# Stepper_control.net
KiCad netlist of a schematic drawn in Altium Designer
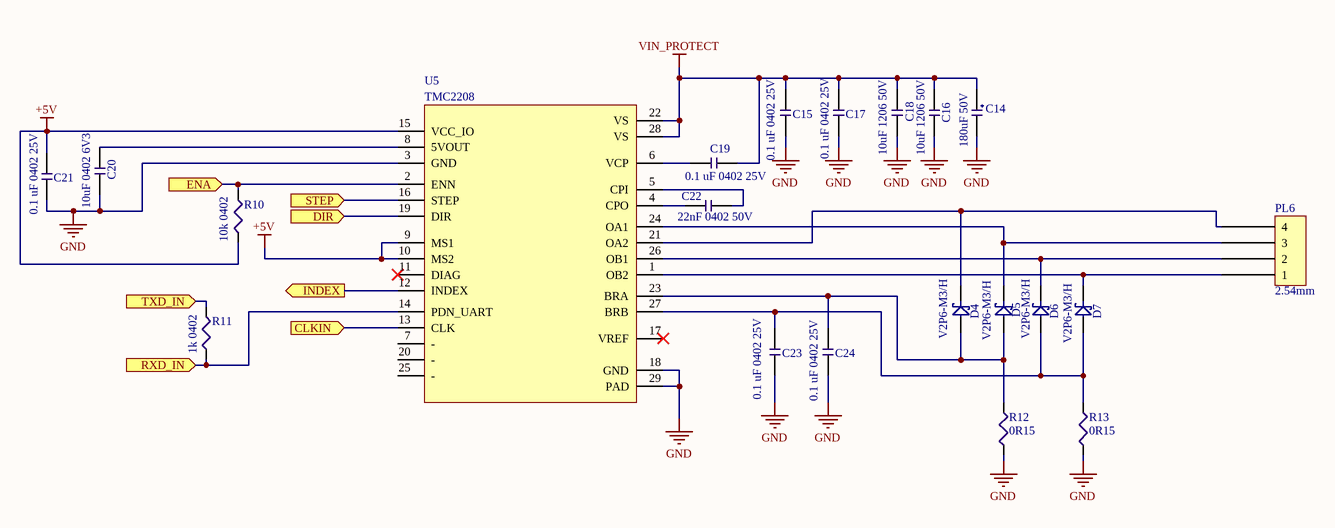
[diagram p0: Stepper_control.SchDoc]

(export (version "E")
  (design (tool "Eeschema 10.0.6"))
  (components
    (comp (ref "C14")
      (value "180uF 50V")
      (footprint "Capacitor 8x22")
      (description "180UF 20% 50V 105DEG RADIAL")
      (fields (field (name "TOLERANCE") "20%"))
      (libsource (lib "ON Development Vault") (part "Polar capacitor"))
    )
    (comp (ref "C15")
      (value "0.1 uF 0402 25V")
      (footprint "CAP_0402")
      (description "0.1UF 25V 10% X5R 0402")
      (fields (field (name "TOLERANCE") "10%") (field (name "VOLTAGE") "25V"))
      (libsource (lib "ON Development Vault") (part "Capacitor"))
    )
    (comp (ref "C16")
      (value "10uF 1206 50V")
      (footprint "CAP_1206")
      (description "10uF 1206 50V X5R 20%")
      (fields (field (name "TOLERANCE") "+/- 20%") (field (name "VOLTAGE") "50 V"))
      (libsource (lib "ON Development Vault") (part "Capacitor"))
    )
    (comp (ref "C17")
      (value "0.1 uF 0402 25V")
      (footprint "CAP_0402")
      (description "0.1UF 25V 10% X5R 0402")
      (fields (field (name "TOLERANCE") "10%") (field (name "VOLTAGE") "25V"))
      (libsource (lib "ON Development Vault") (part "Capacitor"))
    )
    (comp (ref "C18")
      (value "10uF 1206 50V")
      (footprint "CAP_1206")
      (description "10uF 1206 50V X5R 20%")
      (fields (field (name "TOLERANCE") "+/- 20%") (field (name "VOLTAGE") "50 V"))
      (libsource (lib "ON Development Vault") (part "Capacitor"))
    )
    (comp (ref "C19")
      (value "0.1 uF 0402 25V")
      (footprint "CAP_0402")
      (description "0.1UF 25V 10% X5R 0402")
      (fields (field (name "TOLERANCE") "10%") (field (name "VOLTAGE") "25V"))
      (libsource (lib "ON Development Vault") (part "Capacitor"))
    )
    (comp (ref "C20")
      (value "10uF 0402 6V3")
      (footprint "CAP_0402")
      (description "10uF 20% 0402 6V3 X6S")
      (fields (field (name "TOLERANCE") "20%") (field (name "VOLTAGE") "6V3"))
      (libsource (lib "ON Development Vault") (part "Capacitor"))
    )
    (comp (ref "C21")
      (value "0.1 uF 0402 25V")
      (footprint "CAP_0402")
      (description "0.1UF 25V 10% X5R 0402")
      (fields (field (name "TOLERANCE") "10%") (field (name "VOLTAGE") "25V"))
      (libsource (lib "ON Development Vault") (part "Capacitor"))
    )
    (comp (ref "C22")
      (value "22nF 0402 50V")
      (footprint "CAP_0402")
      (description "22nF 0402 50V X7R 10%")
      (fields (field (name "TOLERANCE") "10%") (field (name "VOLTAGE") "50V"))
      (libsource (lib "ON Development Vault") (part "Capacitor"))
    )
    (comp (ref "C23")
      (value "0.1 uF 0402 25V")
      (footprint "CAP_0402")
      (description "0.1UF 25V 10% X5R 0402")
      (fields (field (name "TOLERANCE") "10%") (field (name "VOLTAGE") "25V"))
      (libsource (lib "ON Development Vault") (part "Capacitor"))
    )
    (comp (ref "C24")
      (value "0.1 uF 0402 25V")
      (footprint "CAP_0402")
      (description "0.1UF 25V 10% X5R 0402")
      (fields (field (name "TOLERANCE") "10%") (field (name "VOLTAGE") "25V"))
      (libsource (lib "ON Development Vault") (part "Capacitor"))
    )
    (comp (ref "D4")
      (value "V2P6-M3/H")
      (footprint "MicroSMP")
      (description "DIODE SCHOTTKY 60V 2A MICROSMP")
      (libsource (lib "ON Development Vault") (part "Schottky"))
    )
    (comp (ref "D5")
      (value "V2P6-M3/H")
      (footprint "MicroSMP")
      (description "DIODE SCHOTTKY 60V 2A MICROSMP")
      (libsource (lib "ON Development Vault") (part "Schottky"))
    )
    (comp (ref "D6")
      (value "V2P6-M3/H")
      (footprint "MicroSMP")
      (description "DIODE SCHOTTKY 60V 2A MICROSMP")
      (libsource (lib "ON Development Vault") (part "Schottky"))
    )
    (comp (ref "D7")
      (value "V2P6-M3/H")
      (footprint "MicroSMP")
      (description "DIODE SCHOTTKY 60V 2A MICROSMP")
      (libsource (lib "ON Development Vault") (part "Schottky"))
    )
    (comp (ref "PL6")
      (value "2.54mm")
      (footprint "4-pin 2.54mm header")
      (description "Pin header 4-pin 2.54mm male")
      (fields (field (name "MFG. PART NUMBER") "DS1021-1*4SF1-1"))
      (libsource (lib "ON Development Vault") (part "4-pin header"))
    )
    (comp (ref "R10")
      (value "10k 0402")
      (footprint "RES_0402")
      (description "RES SMD 10K OHM 1% 1/16W 0402")
      (fields (field (name "POWER") "1/16 W") (field (name "TOLERANCE") "1 %"))
      (libsource (lib "ON Development Vault") (part "Resistor"))
    )
    (comp (ref "R11")
      (value "1k 0402")
      (footprint "RES_0402")
      (description "RES SMD 1K OHM 1% 1/16W 0402")
      (fields (field (name "POWER") "1/16W") (field (name "TOLERANCE") "1%"))
      (libsource (lib "ON Development Vault") (part "Resistor"))
    )
    (comp (ref "R12")
      (value "0R15")
      (footprint "RES_1206")
      (description "RES 0.15 OHM 1% 1/2W 1206")
      (fields (field (name "TOLERANCE") "1%") (field (name "POWER") "0.5W"))
      (libsource (lib "ON Development Vault") (part "Resistor"))
    )
    (comp (ref "R13")
      (value "0R15")
      (footprint "RES_1206")
      (description "RES 0.15 OHM 1% 1/2W 1206")
      (fields (field (name "TOLERANCE") "1%") (field (name "POWER") "0.5W"))
      (libsource (lib "ON Development Vault") (part "Resistor"))
    )
    (comp (ref "U5")
      (value "TMC2208")
      (footprint "QFN50P500X500X90_HS-29N")
      (description "IC STEPPER MOTOR DRIVER 28QFN")
      (fields (field (name "MFG. PART NUMBER") "TMC2208-LA-T"))
      (libsource (lib "ON Development Vault") (part "TMC2208"))
    )
  )
  (nets
    (net (code "1") (name "+5V") (class "Default")
      (node (ref "C21") (pin "2") (pinfunction "2_2") (pintype "passive"))
      (node (ref "R10") (pin "2") (pinfunction "2_2") (pintype "passive"))
      (node (ref "U5") (pin "10") (pinfunction "MS2_10") (pintype "passive"))
      (node (ref "U5") (pin "15") (pinfunction "VCC_IO_15") (pintype "passive"))
      (node (ref "U5") (pin "9") (pinfunction "MS1_9") (pintype "passive"))
    )
    (net (code "2") (name "/CLKIN") (class "Default")
      (node (ref "U5") (pin "13") (pinfunction "CLK_13") (pintype "passive"))
    )
    (net (code "3") (name "/DIR") (class "Default")
      (node (ref "U5") (pin "19") (pinfunction "DIR_19") (pintype "passive"))
    )
    (net (code "4") (name "/ENA") (class "Default")
      (node (ref "R10") (pin "1") (pinfunction "1_1") (pintype "passive"))
      (node (ref "U5") (pin "2") (pinfunction "ENN_2") (pintype "passive"))
    )
    (net (code "5") (name "/INDEX") (class "Default")
      (node (ref "U5") (pin "12") (pinfunction "INDEX_12") (pintype "passive"))
    )
    (net (code "6") (name "/RXD_IN") (class "Default")
      (node (ref "R11") (pin "1") (pinfunction "1_1") (pintype "passive"))
      (node (ref "U5") (pin "14") (pinfunction "PDN_UART_14") (pintype "passive"))
    )
    (net (code "7") (name "/STEP") (class "Default")
      (node (ref "U5") (pin "16") (pinfunction "STEP_16") (pintype "passive"))
    )
    (net (code "8") (name "/TXD_IN") (class "Default")
      (node (ref "R11") (pin "2") (pinfunction "2_2") (pintype "passive"))
    )
    (net (code "9") (name "GND") (class "Default")
      (node (ref "C14") (pin "2") (pinfunction "2_2") (pintype "passive"))
      (node (ref "C15") (pin "1") (pinfunction "1_1") (pintype "passive"))
      (node (ref "C16") (pin "2") (pinfunction "2_2") (pintype "passive"))
      (node (ref "C17") (pin "1") (pinfunction "1_1") (pintype "passive"))
      (node (ref "C18") (pin "2") (pinfunction "2_2") (pintype "passive"))
      (node (ref "C20") (pin "1") (pinfunction "1_1") (pintype "passive"))
      (node (ref "C21") (pin "1") (pinfunction "1_1") (pintype "passive"))
      (node (ref "C23") (pin "1") (pinfunction "1_1") (pintype "passive"))
      (node (ref "C24") (pin "1") (pinfunction "1_1") (pintype "passive"))
      (node (ref "R12") (pin "1") (pinfunction "1_1") (pintype "passive"))
      (node (ref "R13") (pin "1") (pinfunction "1_1") (pintype "passive"))
      (node (ref "U5") (pin "18") (pinfunction "GND_18") (pintype "passive"))
      (node (ref "U5") (pin "29") (pinfunction "PAD_29") (pintype "passive"))
      (node (ref "U5") (pin "3") (pinfunction "GND_3") (pintype "passive"))
    )
    (net (code "10") (name "Net-(U5-5VOUT)") (class "Default")
      (node (ref "C20") (pin "2") (pinfunction "2_2") (pintype "passive"))
      (node (ref "U5") (pin "8") (pinfunction "5VOUT_8") (pintype "passive"))
    )
    (net (code "11") (name "Net-(U5-BRA)") (class "Default")
      (node (ref "C24") (pin "2") (pinfunction "2_2") (pintype "passive"))
      (node (ref "D4") (pin "1") (pinfunction "1_1") (pintype "passive"))
      (node (ref "D5") (pin "1") (pinfunction "1_1") (pintype "passive"))
      (node (ref "R12") (pin "2") (pinfunction "2_2") (pintype "passive"))
      (node (ref "U5") (pin "23") (pinfunction "BRA_23") (pintype "passive"))
    )
    (net (code "12") (name "Net-(U5-BRB)") (class "Default")
      (node (ref "C23") (pin "2") (pinfunction "2_2") (pintype "passive"))
      (node (ref "D6") (pin "1") (pinfunction "1_1") (pintype "passive"))
      (node (ref "D7") (pin "1") (pinfunction "1_1") (pintype "passive"))
      (node (ref "R13") (pin "2") (pinfunction "2_2") (pintype "passive"))
      (node (ref "U5") (pin "27") (pinfunction "BRB_27") (pintype "passive"))
    )
    (net (code "13") (name "Net-(U5-CPI)") (class "Default")
      (node (ref "C22") (pin "2") (pinfunction "2_2") (pintype "passive"))
      (node (ref "U5") (pin "5") (pinfunction "CPI_5") (pintype "passive"))
    )
    (net (code "14") (name "Net-(U5-CPO)") (class "Default")
      (node (ref "C22") (pin "1") (pinfunction "1_1") (pintype "passive"))
      (node (ref "U5") (pin "4") (pinfunction "CPO_4") (pintype "passive"))
    )
    (net (code "15") (name "Net-(U5-OA1)") (class "Default")
      (node (ref "D5") (pin "2") (pinfunction "2_2") (pintype "passive"))
      (node (ref "PL6") (pin "3") (pinfunction "3_3") (pintype "passive"))
      (node (ref "U5") (pin "24") (pinfunction "OA1_24") (pintype "passive"))
    )
    (net (code "16") (name "Net-(U5-OA2)") (class "Default")
      (node (ref "D4") (pin "2") (pinfunction "2_2") (pintype "passive"))
      (node (ref "PL6") (pin "4") (pinfunction "4_4") (pintype "passive"))
      (node (ref "U5") (pin "21") (pinfunction "OA2_21") (pintype "passive"))
    )
    (net (code "17") (name "Net-(U5-OB1)") (class "Default")
      (node (ref "D6") (pin "2") (pinfunction "2_2") (pintype "passive"))
      (node (ref "PL6") (pin "2") (pinfunction "2_2") (pintype "passive"))
      (node (ref "U5") (pin "26") (pinfunction "OB1_26") (pintype "passive"))
    )
    (net (code "18") (name "Net-(U5-OB2)") (class "Default")
      (node (ref "D7") (pin "2") (pinfunction "2_2") (pintype "passive"))
      (node (ref "PL6") (pin "1") (pinfunction "1_1") (pintype "passive"))
      (node (ref "U5") (pin "1") (pinfunction "OB2_1") (pintype "passive"))
    )
    (net (code "19") (name "Net-(U5-VCP)") (class "Default")
      (node (ref "C19") (pin "2") (pinfunction "2_2") (pintype "passive"))
      (node (ref "U5") (pin "6") (pinfunction "VCP_6") (pintype "passive"))
    )
    (net (code "20") (name "VIN_PROTECT") (class "Default")
      (node (ref "C14") (pin "1") (pinfunction "1_1") (pintype "passive"))
      (node (ref "C15") (pin "2") (pinfunction "2_2") (pintype "passive"))
      (node (ref "C16") (pin "1") (pinfunction "1_1") (pintype "passive"))
      (node (ref "C17") (pin "2") (pinfunction "2_2") (pintype "passive"))
      (node (ref "C18") (pin "1") (pinfunction "1_1") (pintype "passive"))
      (node (ref "C19") (pin "1") (pinfunction "1_1") (pintype "passive"))
      (node (ref "U5") (pin "22") (pinfunction "VS_22") (pintype "passive"))
      (node (ref "U5") (pin "28") (pinfunction "VS_28") (pintype "passive"))
    )
    (net (code "21") (name "unconnected-(U5---Pad7)") (class "Default")
      (node (ref "U5") (pin "7") (pinfunction "-_7") (pintype "passive"))
    )
    (net (code "22") (name "unconnected-(U5---Pad20)") (class "Default")
      (node (ref "U5") (pin "20") (pinfunction "-_20") (pintype "passive"))
    )
    (net (code "23") (name "unconnected-(U5---Pad25)") (class "Default")
      (node (ref "U5") (pin "25") (pinfunction "-_25") (pintype "passive"))
    )
    (net (code "24") (name "unconnected-(U5-DIAG-Pad11)") (class "Default")
      (node (ref "U5") (pin "11") (pinfunction "DIAG_11") (pintype "passive+no_connect"))
    )
    (net (code "25") (name "unconnected-(U5-VREF-Pad17)") (class "Default")
      (node (ref "U5") (pin "17") (pinfunction "VREF_17") (pintype "passive+no_connect"))
    )
  )
)
